# BrauV2_Etherent.net
KiCad netlist of a schematic drawn in Altium Designer
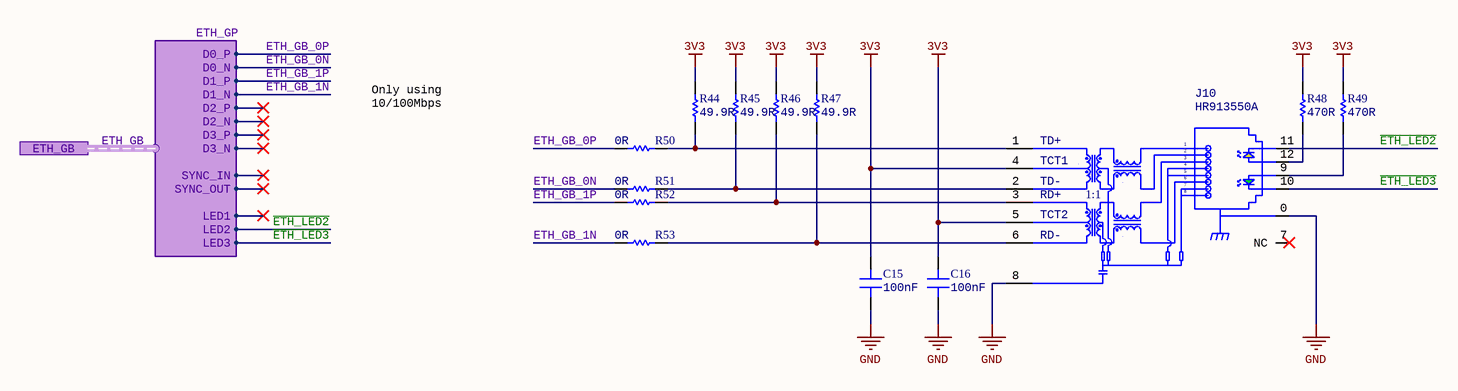
[diagram p0: BrauV2_Etherent.SchDoc]

(export (version "E")
  (design (tool "Eeschema 10.0.6"))
  (components
    (comp (ref "C15")
      (value "CC0402KRX5R9BB104")
      (footprint "SMD_CAP_0402(1005)_N")
      (description "100nF ±10% 50V X5R 0402 Multilayer Ceramic Capacitors MLCC - SMD/SMT RoHS")
      (fields (field (name "TOLERANCE") "10%") (field (name "CAPACITANCE") "100nF"))
      (libsource (lib "BrauV2_Capacitor") (part "100nF 0402 50V 10%"))
    )
    (comp (ref "C16")
      (value "CC0402KRX5R9BB104")
      (footprint "SMD_CAP_0402(1005)_N")
      (description "100nF ±10% 50V X5R 0402 Multilayer Ceramic Capacitors MLCC - SMD/SMT RoHS")
      (fields (field (name "TOLERANCE") "10%") (field (name "CAPACITANCE") "100nF"))
      (libsource (lib "BrauV2_Capacitor") (part "100nF 0402 50V 10%"))
    )
    (comp (ref "J10")
      (value "HR913550A")
      (footprint "HR913550A")
      (description "RJ45 12 1 Green - Yellow Through Hole Ethernet Connectors/Modular Connectors (RJ45 RJ11) RoHS")
      (libsource (lib "BrauV2_Connector") (part "HR913550A"))
    )
    (comp (ref "R44")
      (value "RC0402FR-0749R9L")
      (footprint "SMD_RES_0402(1005)_N")
      (description "49.9Ω ±1% 1/16W ±100ppm/℃ 0402 Chip Resistor - Surface Mount RoHS")
      (fields (field (name "TOLERANCE") "1%") (field (name "RESISTANCE") "49.9R"))
      (libsource (lib "BrauV2_Resistor") (part "49R9 0402 1% 1/16W"))
    )
    (comp (ref "R45")
      (value "RC0402FR-0749R9L")
      (footprint "SMD_RES_0402(1005)_N")
      (description "49.9Ω ±1% 1/16W ±100ppm/℃ 0402 Chip Resistor - Surface Mount RoHS")
      (fields (field (name "TOLERANCE") "1%") (field (name "RESISTANCE") "49.9R"))
      (libsource (lib "BrauV2_Resistor") (part "49R9 0402 1% 1/16W"))
    )
    (comp (ref "R46")
      (value "RC0402FR-0749R9L")
      (footprint "SMD_RES_0402(1005)_N")
      (description "49.9Ω ±1% 1/16W ±100ppm/℃ 0402 Chip Resistor - Surface Mount RoHS")
      (fields (field (name "TOLERANCE") "1%") (field (name "RESISTANCE") "49.9R"))
      (libsource (lib "BrauV2_Resistor") (part "49R9 0402 1% 1/16W"))
    )
    (comp (ref "R47")
      (value "RC0402FR-0749R9L")
      (footprint "SMD_RES_0402(1005)_N")
      (description "49.9Ω ±1% 1/16W ±100ppm/℃ 0402 Chip Resistor - Surface Mount RoHS")
      (fields (field (name "TOLERANCE") "1%") (field (name "RESISTANCE") "49.9R"))
      (libsource (lib "BrauV2_Resistor") (part "49R9 0402 1% 1/16W"))
    )
    (comp (ref "R48")
      (value "RC0402FR-07470RL")
      (footprint "SMD_RES_0402(1005)_N")
      (description "470Ω ±1% 1/16W ±100ppm/℃ 0402 Chip Resistor - Surface Mount RoHS")
      (fields (field (name "TOLERANCE") "1%") (field (name "RESISTANCE") "470R"))
      (libsource (lib "BrauV2_Resistor") (part "470R 0402 1% 1W"))
    )
    (comp (ref "R49")
      (value "RC0402FR-07470RL")
      (footprint "SMD_RES_0402(1005)_N")
      (description "470Ω ±1% 1/16W ±100ppm/℃ 0402 Chip Resistor - Surface Mount RoHS")
      (fields (field (name "TOLERANCE") "1%") (field (name "RESISTANCE") "470R"))
      (libsource (lib "BrauV2_Resistor") (part "470R 0402 1% 1W"))
    )
    (comp (ref "R50")
      (value "RC0402FR-070RL")
      (footprint "SMD_RES_0402(1005)_N")
      (description "0Ω ±1% 1/16W 0402 Chip Resistor - Surface Mount RoHS")
      (fields (field (name "TOLERANCE") "1%") (field (name "RESISTANCE") "0R"))
      (libsource (lib "BrauV2_Resistor") (part "0R 0402 1% 1/16W"))
    )
    (comp (ref "R51")
      (value "RC0402FR-070RL")
      (footprint "SMD_RES_0402(1005)_N")
      (description "0Ω ±1% 1/16W 0402 Chip Resistor - Surface Mount RoHS")
      (fields (field (name "TOLERANCE") "1%") (field (name "RESISTANCE") "0R"))
      (libsource (lib "BrauV2_Resistor") (part "0R 0402 1% 1/16W"))
    )
    (comp (ref "R52")
      (value "RC0402FR-070RL")
      (footprint "SMD_RES_0402(1005)_N")
      (description "0Ω ±1% 1/16W 0402 Chip Resistor - Surface Mount RoHS")
      (fields (field (name "TOLERANCE") "1%") (field (name "RESISTANCE") "0R"))
      (libsource (lib "BrauV2_Resistor") (part "0R 0402 1% 1/16W"))
    )
    (comp (ref "R53")
      (value "RC0402FR-070RL")
      (footprint "SMD_RES_0402(1005)_N")
      (description "0Ω ±1% 1/16W 0402 Chip Resistor - Surface Mount RoHS")
      (fields (field (name "TOLERANCE") "1%") (field (name "RESISTANCE") "0R"))
      (libsource (lib "BrauV2_Resistor") (part "0R 0402 1% 1/16W"))
    )
  )
  (nets
    (net (code "2") (name "/ETH_GB_0N") (class "Default")
      (node (ref "R51") (pin "1") (pinfunction "1_1") (pintype "passive"))
    )
    (net (code "3") (name "/ETH_GB_0P") (class "Default")
      (node (ref "R50") (pin "1") (pinfunction "1_1") (pintype "passive"))
    )
    (net (code "4") (name "/ETH_GB_1N") (class "Default")
      (node (ref "R53") (pin "1") (pinfunction "1_1") (pintype "passive"))
    )
    (net (code "5") (name "/ETH_GB_1P") (class "Default")
      (node (ref "R52") (pin "1") (pinfunction "1_1") (pintype "passive"))
    )
    (net (code "7") (name "/~{ETH_LED2}") (class "Default")
      (node (ref "J10") (pin "11") (pinfunction "YLED-_11") (pintype "passive"))
    )
    (net (code "8") (name "/~{ETH_LED3}") (class "Default")
      (node (ref "J10") (pin "10") (pinfunction "GLED+_10") (pintype "passive"))
    )
    (net (code "9") (name "3V3") (class "Default")
      (node (ref "C15") (pin "2") (pinfunction "2_2") (pintype "passive"))
      (node (ref "C16") (pin "2") (pinfunction "2_2") (pintype "passive"))
      (node (ref "J10") (pin "4") (pinfunction "TCT1_4") (pintype "passive"))
      (node (ref "J10") (pin "5") (pinfunction "TCT2_5") (pintype "passive"))
      (node (ref "R44") (pin "2") (pinfunction "2_2") (pintype "passive"))
      (node (ref "R45") (pin "2") (pinfunction "2_2") (pintype "passive"))
      (node (ref "R46") (pin "2") (pinfunction "2_2") (pintype "passive"))
      (node (ref "R47") (pin "2") (pinfunction "2_2") (pintype "passive"))
      (node (ref "R48") (pin "2") (pinfunction "2_2") (pintype "passive"))
      (node (ref "R49") (pin "2") (pinfunction "2_2") (pintype "passive"))
    )
    (net (code "10") (name "GND") (class "Default")
      (node (ref "C15") (pin "1") (pinfunction "1_1") (pintype "passive"))
      (node (ref "C16") (pin "1") (pinfunction "1_1") (pintype "passive"))
      (node (ref "J10") (pin "0") (pinfunction "SHLD_0") (pintype "passive"))
      (node (ref "J10") (pin "8") (pinfunction "GND_8") (pintype "passive"))
    )
    (net (code "11") (name "Net-(J10-OLED+)") (class "Default")
      (node (ref "J10") (pin "9") (pinfunction "OLED+_9") (pintype "passive"))
      (node (ref "R49") (pin "1") (pinfunction "1_1") (pintype "passive"))
    )
    (net (code "12") (name "Net-(J10-RD+)") (class "Default")
      (node (ref "J10") (pin "3") (pinfunction "RD+_3") (pintype "passive"))
      (node (ref "R46") (pin "1") (pinfunction "1_1") (pintype "passive"))
      (node (ref "R52") (pin "2") (pinfunction "2_2") (pintype "passive"))
    )
    (net (code "13") (name "Net-(J10-RD-)") (class "Default")
      (node (ref "J10") (pin "6") (pinfunction "RD-_6") (pintype "passive"))
      (node (ref "R47") (pin "1") (pinfunction "1_1") (pintype "passive"))
      (node (ref "R53") (pin "2") (pinfunction "2_2") (pintype "passive"))
    )
    (net (code "14") (name "Net-(J10-TD+)") (class "Default")
      (node (ref "J10") (pin "1") (pinfunction "TD+_1") (pintype "passive"))
      (node (ref "R44") (pin "1") (pinfunction "1_1") (pintype "passive"))
      (node (ref "R50") (pin "2") (pinfunction "2_2") (pintype "passive"))
    )
    (net (code "15") (name "Net-(J10-TD-)") (class "Default")
      (node (ref "J10") (pin "2") (pinfunction "TD-_2") (pintype "passive"))
      (node (ref "R45") (pin "1") (pinfunction "1_1") (pintype "passive"))
      (node (ref "R51") (pin "2") (pinfunction "2_2") (pintype "passive"))
    )
    (net (code "16") (name "Net-(J10-YLED+)") (class "Default")
      (node (ref "J10") (pin "12") (pinfunction "YLED+_12") (pintype "passive"))
      (node (ref "R48") (pin "1") (pinfunction "1_1") (pintype "passive"))
    )
    (net (code "17") (name "unconnected-(J10-NC-Pad7)") (class "Default")
      (node (ref "J10") (pin "7") (pinfunction "NC_7") (pintype "passive+no_connect"))
    )
  )
)
